# small.net
KiCad netlist of a schematic drawn in EAGLE
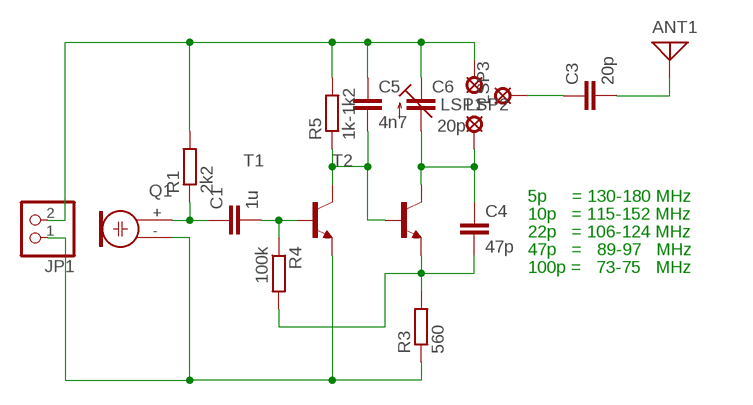
[diagram p0: schematic, sheet 1]

(export (version "E")
  (design (tool "Eeschema 10.0.6"))
  (components
    (comp (ref "ANT1")
      (value "ANTENNA")
      (footprint "eagle-import:PAD-01")
      (libsource (lib "eagle-import") (part "ANTENNA"))
    )
    (comp (ref "C1")
      (value "1u")
      (footprint "eagle-import:C025-025X050")
      (libsource (lib "eagle-import") (part "C-EU025-025X050"))
    )
    (comp (ref "C3")
      (value "20p")
      (footprint "eagle-import:C025-025X050")
      (libsource (lib "eagle-import") (part "C-EU025-025X050"))
    )
    (comp (ref "C4")
      (value "47p")
      (footprint "eagle-import:C025-025X050")
      (libsource (lib "eagle-import") (part "C-EU025-025X050"))
    )
    (comp (ref "C5")
      (value "4n7")
      (footprint "eagle-import:C025-025X050")
      (libsource (lib "eagle-import") (part "C-EU025-025X050"))
    )
    (comp (ref "C6")
      (value "20p")
      (footprint "eagle-import:CTRIM808-BC")
      (libsource (lib "eagle-import") (part "C-TRIMM808"))
    )
    (comp (ref "JP1")
      (value "PINHD-1X2")
      (footprint "eagle-import:1X02")
      (libsource (lib "eagle-import") (part "PINHD-1X2"))
    )
    (comp (ref "LSP1")
      (value "SE14")
      (footprint "eagle-import:SE14")
      (libsource (lib "eagle-import") (part "SE14"))
    )
    (comp (ref "LSP2")
      (value "SE14")
      (footprint "eagle-import:SE14")
      (libsource (lib "eagle-import") (part "SE14"))
    )
    (comp (ref "LSP3")
      (value "SE14")
      (footprint "eagle-import:SE14")
      (libsource (lib "eagle-import") (part "SE14"))
    )
    (comp (ref "Q1")
      (value "ELECTRET")
      (footprint "eagle-import:9.7ELECTRET")
      (libsource (lib "eagle-import") (part "ELECTRET"))
    )
    (comp (ref "R1")
      (value "2k2")
      (footprint "eagle-import:0207_2V")
      (libsource (lib "eagle-import") (part "R-EU_0207/2V"))
    )
    (comp (ref "R3")
      (value "560")
      (footprint "eagle-import:0207_2V")
      (libsource (lib "eagle-import") (part "R-EU_0207/2V"))
    )
    (comp (ref "R4")
      (value "100k")
      (footprint "eagle-import:0207_2V")
      (libsource (lib "eagle-import") (part "R-EU_0207/2V"))
    )
    (comp (ref "R5")
      (value "1k-1k2")
      (footprint "eagle-import:0207_2V")
      (libsource (lib "eagle-import") (part "R-EU_0207/2V"))
    )
    (comp (ref "T1")
      (value "BC547-NPN-TO92-CBE")
      (footprint "eagle-import:TO92-CBE")
      (libsource (lib "eagle-import") (part "-NPN-TO92-CBEBC547"))
    )
    (comp (ref "T2")
      (value "BC547-NPN-TO92-CBE")
      (footprint "eagle-import:TO92-CBE")
      (libsource (lib "eagle-import") (part "-NPN-TO92-CBEBC547"))
    )
  )
  (nets
    (net (code "1") (name "Net-(ANT1-Pad1)") (class "Default")
      (node (ref "ANT1") (pin "1") (pinfunction "1_1") (pintype "output"))
      (node (ref "C3") (pin "2") (pinfunction "2_2") (pintype "passive"))
    )
    (net (code "2") (name "Net-(C1-Pad2)") (class "Default")
      (node (ref "C1") (pin "2") (pinfunction "2_2") (pintype "passive"))
      (node (ref "R4") (pin "1") (pinfunction "1_1") (pintype "passive"))
      (node (ref "T1") (pin "B") (pinfunction "B_B") (pintype "passive"))
    )
    (net (code "3") (name "Net-(C3-Pad1)") (class "Default")
      (node (ref "C3") (pin "1") (pinfunction "1_1") (pintype "passive"))
      (node (ref "LSP3") (pin "MP") (pinfunction "MP_MP") (pintype "passive"))
    )
    (net (code "4") (name "Net-(C4-Pad2)") (class "Default")
      (node (ref "C4") (pin "2") (pinfunction "2_2") (pintype "passive"))
      (node (ref "R3") (pin "2") (pinfunction "2_2") (pintype "passive"))
      (node (ref "R4") (pin "2") (pinfunction "2_2") (pintype "passive"))
      (node (ref "T2") (pin "E") (pinfunction "E_E") (pintype "passive"))
    )
    (net (code "5") (name "Net-(C5-Pad2)") (class "Default")
      (node (ref "C5") (pin "2") (pinfunction "2_2") (pintype "passive"))
      (node (ref "R5") (pin "1") (pinfunction "1_1") (pintype "passive"))
      (node (ref "T1") (pin "C") (pinfunction "C_C") (pintype "passive"))
      (node (ref "T2") (pin "B") (pinfunction "B_B") (pintype "passive"))
    )
    (net (code "6") (name "Net-(C6-A)") (class "Default")
      (node (ref "C4") (pin "1") (pinfunction "1_1") (pintype "passive"))
      (node (ref "C6") (pin "2") (pinfunction "A_2") (pintype "passive"))
      (node (ref "LSP2") (pin "MP") (pinfunction "MP_MP") (pintype "passive"))
      (node (ref "T2") (pin "C") (pinfunction "C_C") (pintype "passive"))
    )
    (net (code "7") (name "Net-(C6-E)") (class "Default")
      (node (ref "C5") (pin "1") (pinfunction "1_1") (pintype "passive"))
      (node (ref "C6") (pin "1") (pinfunction "E_1") (pintype "passive"))
      (node (ref "JP1") (pin "2") (pinfunction "2_2") (pintype "passive"))
      (node (ref "LSP1") (pin "MP") (pinfunction "MP_MP") (pintype "passive"))
      (node (ref "R1") (pin "2") (pinfunction "2_2") (pintype "passive"))
      (node (ref "R5") (pin "2") (pinfunction "2_2") (pintype "passive"))
    )
    (net (code "8") (name "Net-(Q1-1)") (class "Default")
      (node (ref "JP1") (pin "1") (pinfunction "1_1") (pintype "passive"))
      (node (ref "Q1") (pin "-") (pinfunction "1_-") (pintype "passive"))
      (node (ref "R3") (pin "1") (pinfunction "1_1") (pintype "passive"))
      (node (ref "T1") (pin "E") (pinfunction "E_E") (pintype "passive"))
    )
    (net (code "9") (name "Net-(Q1-2)") (class "Default")
      (node (ref "C1") (pin "1") (pinfunction "1_1") (pintype "passive"))
      (node (ref "Q1") (pin "+") (pinfunction "2_+") (pintype "passive"))
      (node (ref "R1") (pin "1") (pinfunction "1_1") (pintype "passive"))
    )
  )
)
